# Sheet1.net
KiCad netlist of a schematic drawn in Altium Designer
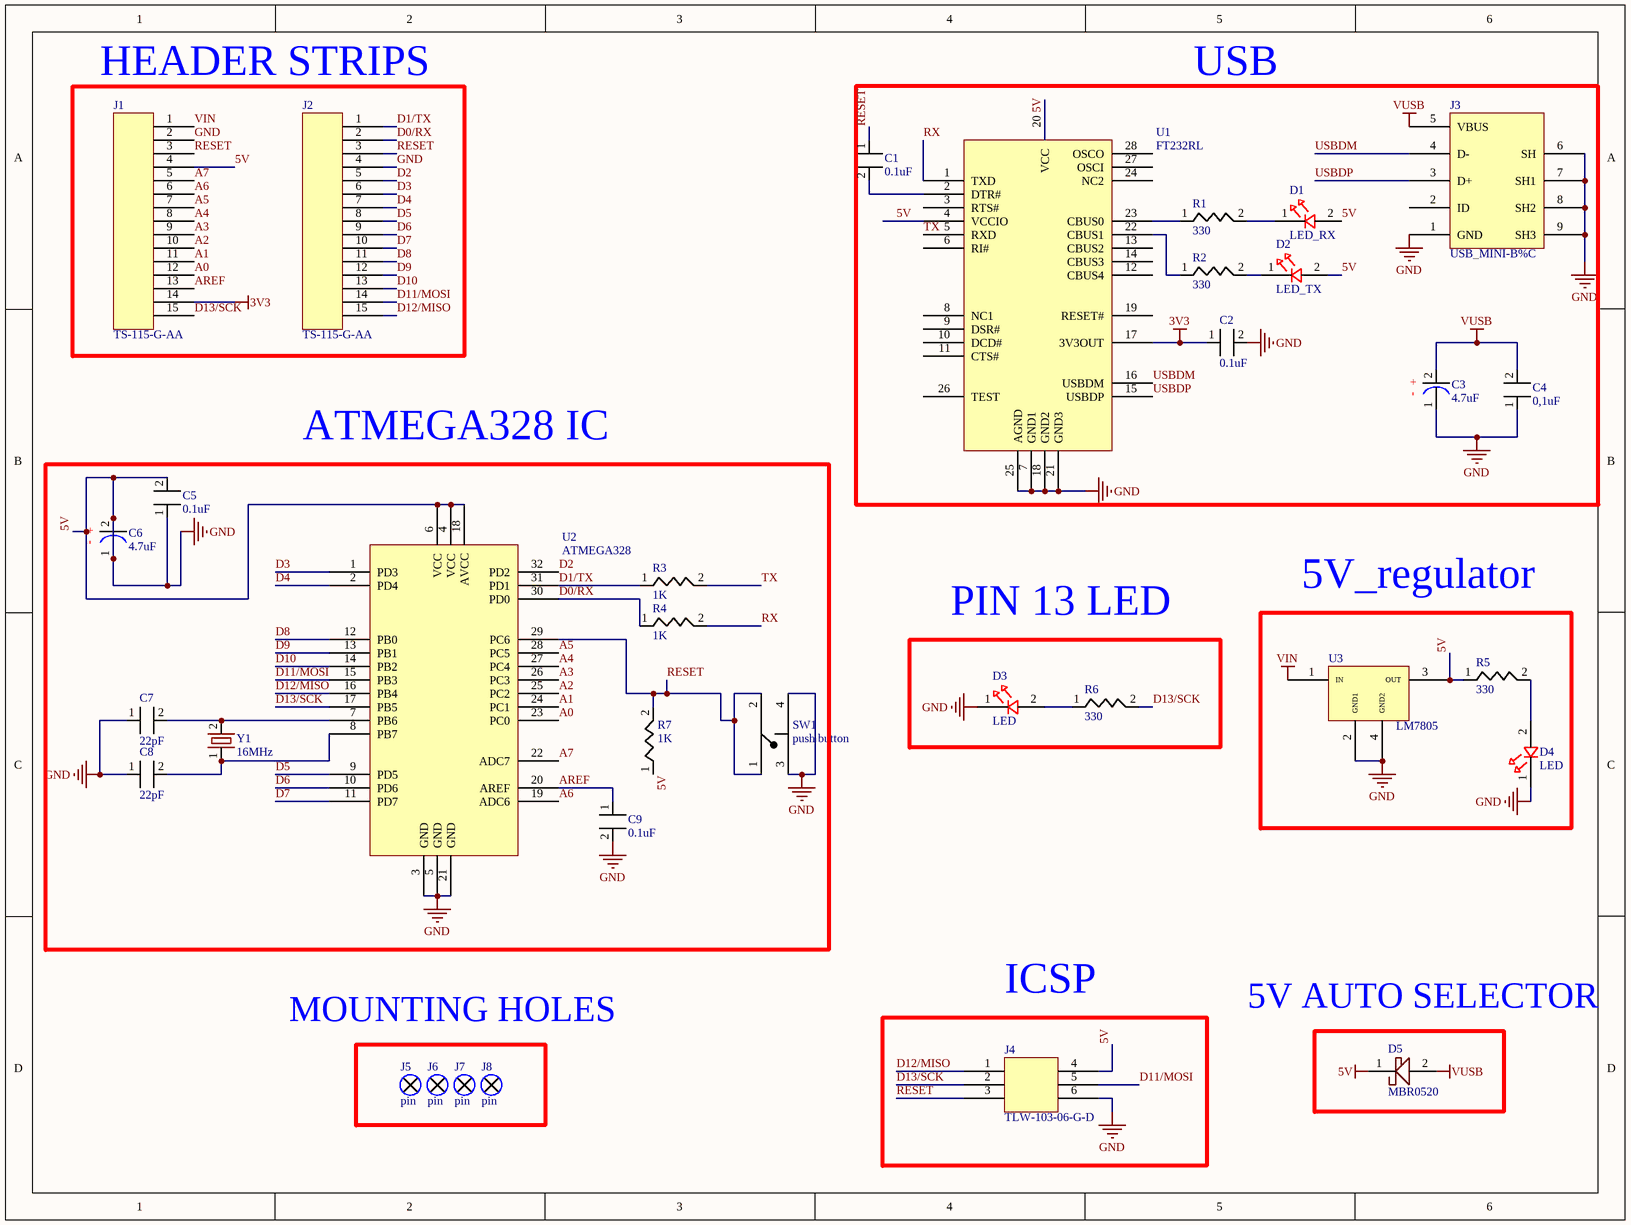
[diagram p0: Sheet1.SchDoc]

(export (version "E")
  (design (tool "Eeschema 10.0.6"))
  (components
    (comp (ref "C1") (value "0.1uF") (footprint "Capacitor") (libsource (lib "Schlib1") (part "capacitor")))
    (comp (ref "C2") (value "0.1uF") (footprint "Capacitor") (libsource (lib "Schlib1") (part "capacitor")))
    (comp (ref "C3")
      (value "4.7uF")
      (footprint "polar Capacitor")
      (libsource (lib "Schlib1") (part "polarized capcitor"))
    )
    (comp (ref "C4") (value "0,1uF") (footprint "Capacitor") (libsource (lib "Schlib1") (part "capacitor")))
    (comp (ref "C5") (value "0.1uF") (footprint "Capacitor") (libsource (lib "Schlib1") (part "capacitor")))
    (comp (ref "C6")
      (value "4.7uF")
      (footprint "polar Capacitor")
      (libsource (lib "Schlib1") (part "polarized capcitor"))
    )
    (comp (ref "C7") (value "22pF") (footprint "Capacitor") (libsource (lib "Schlib1") (part "capacitor")))
    (comp (ref "C8") (value "22pF") (footprint "Capacitor") (libsource (lib "Schlib1") (part "capacitor")))
    (comp (ref "C9") (value "0.1uF") (footprint "Capacitor") (libsource (lib "Schlib1") (part "capacitor")))
    (comp (ref "D1") (value "LED_RX") (footprint "LED") (libsource (lib "Schlib1") (part "LED")))
    (comp (ref "D2") (value "LED_TX") (footprint "LED") (libsource (lib "Schlib1") (part "LED")))
    (comp (ref "D3") (value "LED") (footprint "LED") (libsource (lib "Schlib1") (part "LED")))
    (comp (ref "D4") (value "LED") (footprint "LED") (libsource (lib "Schlib1") (part "LED")))
    (comp (ref "D5") (value "MBR0520") (footprint "MBR0520") (libsource (lib "Schlib1") (part "MBR0520")))
    (comp (ref "J1")
      (value "TS-115-G-AA")
      (footprint "PCBComponent_1")
      (libsource (lib "Schlib1") (part "Component_1"))
    )
    (comp (ref "J2")
      (value "TS-115-G-AA")
      (footprint "PCBComponent_1")
      (libsource (lib "Schlib1") (part "Component_1"))
    )
    (comp (ref "J3")
      (value "USB_MINI-B%C")
      (footprint "USB MINI_B")
      (libsource (lib "Schlib1") (part "USB_MINI-B%C"))
    )
    (comp (ref "J4")
      (value "TLW-103-06-G-D")
      (footprint "pin header3x2")
      (libsource (lib "Schlib1") (part "pin header3x2"))
    )
    (comp (ref "J5") (value "pin") (footprint "PIN") (libsource (lib "Schlib1") (part "pin")))
    (comp (ref "J6") (value "pin") (footprint "PIN") (libsource (lib "Schlib1") (part "pin")))
    (comp (ref "J7") (value "pin") (footprint "PIN") (libsource (lib "Schlib1") (part "pin")))
    (comp (ref "J8") (value "pin") (footprint "PIN") (libsource (lib "Schlib1") (part "pin")))
    (comp (ref "R1") (value "330") (footprint "Resistor") (libsource (lib "Schlib1") (part "resistor")))
    (comp (ref "R2") (value "330") (footprint "Resistor") (libsource (lib "Schlib1") (part "resistor")))
    (comp (ref "R3") (value "1K") (footprint "Resistor") (libsource (lib "Schlib1") (part "resistor")))
    (comp (ref "R4") (value "1K") (footprint "Resistor") (libsource (lib "Schlib1") (part "resistor")))
    (comp (ref "R5") (value "330") (footprint "Resistor") (libsource (lib "Schlib1") (part "resistor")))
    (comp (ref "R6") (value "330") (footprint "Resistor") (libsource (lib "Schlib1") (part "resistor")))
    (comp (ref "R7") (value "1K") (footprint "Resistor") (libsource (lib "Schlib1") (part "resistor")))
    (comp (ref "SW1")
      (value "push button")
      (footprint "push button")
      (libsource (lib "Schlib1") (part "push button"))
    )
    (comp (ref "U1") (value "FT232RL") (footprint "FT232RL") (libsource (lib "Schlib1") (part "FT232RL")))
    (comp (ref "U2")
      (value "ATMEGA328")
      (footprint "ATMEGEA328")
      (libsource (lib "Schlib1") (part "ATMEGA328"))
    )
    (comp (ref "U3") (value "LM7805") (footprint "LM7805") (libsource (lib "Schlib1") (part "regulator")))
    (comp (ref "Y1")
      (value "16MHz")
      (footprint "crystal - duplicate")
      (libsource (lib "Schlib1") (part "crystal_dub"))
    )
  )
  (nets
    (net (code "1") (name "/A0") (class "Default")
      (node (ref "J1") (pin "12") (pinfunction "169_12") (pintype "passive"))
      (node (ref "U2") (pin "23") (pinfunction "PC0_23") (pintype "passive"))
    )
    (net (code "2") (name "/A1") (class "Default")
      (node (ref "J1") (pin "11") (pinfunction "168_11") (pintype "passive"))
      (node (ref "U2") (pin "24") (pinfunction "PC1_24") (pintype "passive"))
    )
    (net (code "3") (name "/A2") (class "Default")
      (node (ref "J1") (pin "10") (pinfunction "167_10") (pintype "passive"))
      (node (ref "U2") (pin "25") (pinfunction "PC2_25") (pintype "passive"))
    )
    (net (code "4") (name "/A3") (class "Default")
      (node (ref "J1") (pin "9") (pinfunction "166_9") (pintype "passive"))
      (node (ref "U2") (pin "26") (pinfunction "PC3_26") (pintype "passive"))
    )
    (net (code "5") (name "/A4") (class "Default")
      (node (ref "J1") (pin "8") (pinfunction "165_8") (pintype "passive"))
      (node (ref "U2") (pin "27") (pinfunction "PC4_27") (pintype "passive"))
    )
    (net (code "6") (name "/A5") (class "Default")
      (node (ref "J1") (pin "7") (pinfunction "164_7") (pintype "passive"))
      (node (ref "U2") (pin "28") (pinfunction "PC5_28") (pintype "passive"))
    )
    (net (code "7") (name "/A6") (class "Default")
      (node (ref "J1") (pin "6") (pinfunction "163_6") (pintype "passive"))
      (node (ref "U2") (pin "19") (pinfunction "ADC6_19") (pintype "passive"))
    )
    (net (code "8") (name "/A7") (class "Default")
      (node (ref "J1") (pin "5") (pinfunction "162_5") (pintype "passive"))
      (node (ref "U2") (pin "22") (pinfunction "ADC7_22") (pintype "passive"))
    )
    (net (code "9") (name "/AREF") (class "Default")
      (node (ref "C9") (pin "1") (pinfunction "155_1") (pintype "passive"))
      (node (ref "J1") (pin "13") (pinfunction "170_13") (pintype "passive"))
      (node (ref "U2") (pin "20") (pinfunction "AREF_20") (pintype "passive"))
    )
    (net (code "10") (name "/D0{slash}RX") (class "Default")
      (node (ref "J2") (pin "2") (pinfunction "159_2") (pintype "passive"))
      (node (ref "R4") (pin "1") (pinfunction "153_1") (pintype "passive"))
      (node (ref "U2") (pin "30") (pinfunction "PD0_30") (pintype "passive"))
    )
    (net (code "11") (name "/D1{slash}TX") (class "Default")
      (node (ref "J2") (pin "1") (pinfunction "158_1") (pintype "passive"))
      (node (ref "R3") (pin "1") (pinfunction "153_1") (pintype "passive"))
      (node (ref "U2") (pin "31") (pinfunction "PD1_31") (pintype "passive"))
    )
    (net (code "12") (name "/D2") (class "Default")
      (node (ref "J2") (pin "5") (pinfunction "162_5") (pintype "passive"))
      (node (ref "U2") (pin "32") (pinfunction "PD2_32") (pintype "passive"))
    )
    (net (code "13") (name "/D3") (class "Default")
      (node (ref "J2") (pin "6") (pinfunction "163_6") (pintype "passive"))
      (node (ref "U2") (pin "1") (pinfunction "PD3_1") (pintype "passive"))
    )
    (net (code "14") (name "/D4") (class "Default")
      (node (ref "J2") (pin "7") (pinfunction "164_7") (pintype "passive"))
      (node (ref "U2") (pin "2") (pinfunction "PD4_2") (pintype "passive"))
    )
    (net (code "15") (name "/D5") (class "Default")
      (node (ref "J2") (pin "8") (pinfunction "165_8") (pintype "passive"))
      (node (ref "U2") (pin "9") (pinfunction "PD5_9") (pintype "passive"))
    )
    (net (code "16") (name "/D6") (class "Default")
      (node (ref "J2") (pin "9") (pinfunction "166_9") (pintype "passive"))
      (node (ref "U2") (pin "10") (pinfunction "PD6_10") (pintype "passive"))
    )
    (net (code "17") (name "/D7") (class "Default")
      (node (ref "J2") (pin "10") (pinfunction "167_10") (pintype "passive"))
      (node (ref "U2") (pin "11") (pinfunction "PD7_11") (pintype "passive"))
    )
    (net (code "18") (name "/D8") (class "Default")
      (node (ref "J2") (pin "11") (pinfunction "168_11") (pintype "passive"))
      (node (ref "U2") (pin "12") (pinfunction "PB0_12") (pintype "passive"))
    )
    (net (code "19") (name "/D9") (class "Default")
      (node (ref "J2") (pin "12") (pinfunction "169_12") (pintype "passive"))
      (node (ref "U2") (pin "13") (pinfunction "PB1_13") (pintype "passive"))
    )
    (net (code "20") (name "/D10") (class "Default")
      (node (ref "J2") (pin "13") (pinfunction "170_13") (pintype "passive"))
      (node (ref "U2") (pin "14") (pinfunction "PB2_14") (pintype "passive"))
    )
    (net (code "21") (name "/D11{slash}MOSI") (class "Default")
      (node (ref "J2") (pin "14") (pinfunction "171_14") (pintype "passive"))
      (node (ref "J4") (pin "5") (pinfunction "14_5") (pintype "passive"))
      (node (ref "U2") (pin "15") (pinfunction "PB3_15") (pintype "passive"))
    )
    (net (code "22") (name "/D12{slash}MISO") (class "Default")
      (node (ref "J2") (pin "15") (pinfunction "172_15") (pintype "passive"))
      (node (ref "J4") (pin "1") (pinfunction "10_1") (pintype "passive"))
      (node (ref "U2") (pin "16") (pinfunction "PB4_16") (pintype "passive"))
    )
    (net (code "23") (name "/D13{slash}SCK") (class "Default")
      (node (ref "J1") (pin "15") (pinfunction "172_15") (pintype "passive"))
      (node (ref "J4") (pin "2") (pinfunction "11_2") (pintype "passive"))
      (node (ref "R6") (pin "2") (pinfunction "152_2") (pintype "passive"))
      (node (ref "U2") (pin "17") (pinfunction "PB5_17") (pintype "passive"))
    )
    (net (code "24") (name "/RESET") (class "Default")
      (node (ref "C1") (pin "1") (pinfunction "155_1") (pintype "passive"))
      (node (ref "J1") (pin "3") (pinfunction "160_3") (pintype "passive"))
      (node (ref "J2") (pin "3") (pinfunction "160_3") (pintype "passive"))
      (node (ref "J4") (pin "3") (pinfunction "12_3") (pintype "passive"))
      (node (ref "R7") (pin "2") (pinfunction "152_2") (pintype "passive"))
      (node (ref "SW1") (pin "1") (pinfunction "254_1") (pintype "passive"))
      (node (ref "SW1") (pin "2") (pinfunction "255_2") (pintype "passive"))
      (node (ref "U2") (pin "29") (pinfunction "PC6_29") (pintype "passive"))
    )
    (net (code "25") (name "/RX") (class "Default")
      (node (ref "R4") (pin "2") (pinfunction "152_2") (pintype "passive"))
      (node (ref "U1") (pin "1") (pinfunction "TXD_1") (pintype "passive"))
    )
    (net (code "26") (name "/TX") (class "Default")
      (node (ref "R3") (pin "2") (pinfunction "152_2") (pintype "passive"))
      (node (ref "U1") (pin "5") (pinfunction "RXD_5") (pintype "passive"))
    )
    (net (code "27") (name "/USBDM") (class "Default")
      (node (ref "J3") (pin "4") (pinfunction "D-_4") (pintype "passive"))
      (node (ref "U1") (pin "16") (pinfunction "USBDM_16") (pintype "passive"))
    )
    (net (code "28") (name "/USBDP") (class "Default")
      (node (ref "J3") (pin "3") (pinfunction "D+_3") (pintype "passive"))
      (node (ref "U1") (pin "15") (pinfunction "USBDP_15") (pintype "passive"))
    )
    (net (code "29") (name "3V3") (class "Default")
      (node (ref "C2") (pin "1") (pinfunction "155_1") (pintype "passive"))
      (node (ref "J1") (pin "14") (pinfunction "171_14") (pintype "passive"))
      (node (ref "U1") (pin "17") (pinfunction "3V3OUT_17") (pintype "passive"))
    )
    (net (code "30") (name "5V") (class "Default")
      (node (ref "C2") (pin "2") (pinfunction "154_2") (pintype "passive"))
      (node (ref "C3") (pin "1") (pinfunction "155_1") (pintype "passive"))
      (node (ref "C4") (pin "1") (pinfunction "155_1") (pintype "passive"))
      (node (ref "C5") (pin "1") (pinfunction "155_1") (pintype "passive"))
      (node (ref "C5") (pin "2") (pinfunction "154_2") (pintype "passive"))
      (node (ref "C6") (pin "1") (pinfunction "155_1") (pintype "passive"))
      (node (ref "C6") (pin "2") (pinfunction "154_2") (pintype "passive"))
      (node (ref "C7") (pin "1") (pinfunction "155_1") (pintype "passive"))
      (node (ref "C8") (pin "1") (pinfunction "155_1") (pintype "passive"))
      (node (ref "C9") (pin "2") (pinfunction "154_2") (pintype "passive"))
      (node (ref "D1") (pin "2") (pinfunction "157_2") (pintype "passive"))
      (node (ref "D2") (pin "2") (pinfunction "157_2") (pintype "passive"))
      (node (ref "D3") (pin "1") (pinfunction "156_1") (pintype "passive"))
      (node (ref "D4") (pin "1") (pinfunction "156_1") (pintype "passive"))
      (node (ref "D5") (pin "1") (pinfunction "180_1") (pintype "passive"))
      (node (ref "J1") (pin "2") (pinfunction "159_2") (pintype "passive"))
      (node (ref "J1") (pin "4") (pinfunction "161_4") (pintype "passive"))
      (node (ref "J2") (pin "4") (pinfunction "161_4") (pintype "passive"))
      (node (ref "J3") (pin "1") (pinfunction "GND_1") (pintype "passive"))
      (node (ref "J3") (pin "6") (pinfunction "SH_6") (pintype "passive"))
      (node (ref "J3") (pin "7") (pinfunction "SH1_7") (pintype "passive"))
      (node (ref "J3") (pin "8") (pinfunction "SH2_8") (pintype "passive"))
      (node (ref "J3") (pin "9") (pinfunction "SH3_9") (pintype "passive"))
      (node (ref "J4") (pin "4") (pinfunction "13_4") (pintype "passive"))
      (node (ref "J4") (pin "6") (pinfunction "6_6") (pintype "passive"))
      (node (ref "R5") (pin "1") (pinfunction "153_1") (pintype "passive"))
      (node (ref "R7") (pin "1") (pinfunction "153_1") (pintype "passive"))
      (node (ref "SW1") (pin "3") (pinfunction "256_3") (pintype "passive"))
      (node (ref "SW1") (pin "4") (pinfunction "257_4") (pintype "passive"))
      (node (ref "U1") (pin "18") (pinfunction "GND2_18") (pintype "passive"))
      (node (ref "U1") (pin "20") (pinfunction "VCC_20") (pintype "passive"))
      (node (ref "U1") (pin "21") (pinfunction "GND3_21") (pintype "passive"))
      (node (ref "U1") (pin "25") (pinfunction "AGND_25") (pintype "passive"))
      (node (ref "U1") (pin "4") (pinfunction "VCCIO_4") (pintype "passive"))
      (node (ref "U1") (pin "7") (pinfunction "GND1_7") (pintype "passive"))
      (node (ref "U2") (pin "18") (pinfunction "AVCC_18") (pintype "passive"))
      (node (ref "U2") (pin "21") (pinfunction "GND_21") (pintype "passive"))
      (node (ref "U2") (pin "3") (pinfunction "GND_3") (pintype "passive"))
      (node (ref "U2") (pin "4") (pinfunction "VCC_4") (pintype "passive"))
      (node (ref "U2") (pin "5") (pinfunction "GND_5") (pintype "passive"))
      (node (ref "U2") (pin "6") (pinfunction "VCC_6") (pintype "passive"))
      (node (ref "U3") (pin "2") (pinfunction "GND1_2") (pintype "passive"))
      (node (ref "U3") (pin "3") (pinfunction "OUT_3") (pintype "passive"))
      (node (ref "U3") (pin "4") (pinfunction "GND2_4") (pintype "passive"))
    )
    (net (code "31") (name "Net-(C1-154)") (class "Default")
      (node (ref "C1") (pin "2") (pinfunction "154_2") (pintype "passive"))
      (node (ref "U1") (pin "2") (pinfunction "DTR#_2") (pintype "passive"))
    )
    (net (code "32") (name "Net-(C7-154)") (class "Default")
      (node (ref "C7") (pin "2") (pinfunction "154_2") (pintype "passive"))
      (node (ref "U2") (pin "7") (pinfunction "PB6_7") (pintype "passive"))
      (node (ref "Y1") (pin "2") (pinfunction "253_2") (pintype "passive"))
    )
    (net (code "33") (name "Net-(C8-154)") (class "Default")
      (node (ref "C8") (pin "2") (pinfunction "154_2") (pintype "passive"))
      (node (ref "U2") (pin "8") (pinfunction "PB7_8") (pintype "passive"))
      (node (ref "Y1") (pin "1") (pinfunction "252_1") (pintype "passive"))
    )
    (net (code "34") (name "Net-(D1-156)") (class "Default")
      (node (ref "D1") (pin "1") (pinfunction "156_1") (pintype "passive"))
      (node (ref "R1") (pin "2") (pinfunction "152_2") (pintype "passive"))
    )
    (net (code "35") (name "Net-(D2-156)") (class "Default")
      (node (ref "D2") (pin "1") (pinfunction "156_1") (pintype "passive"))
      (node (ref "R2") (pin "2") (pinfunction "152_2") (pintype "passive"))
    )
    (net (code "36") (name "Net-(D3-157)") (class "Default")
      (node (ref "D3") (pin "2") (pinfunction "157_2") (pintype "passive"))
      (node (ref "R6") (pin "1") (pinfunction "153_1") (pintype "passive"))
    )
    (net (code "37") (name "Net-(D4-157)") (class "Default")
      (node (ref "D4") (pin "2") (pinfunction "157_2") (pintype "passive"))
      (node (ref "R5") (pin "2") (pinfunction "152_2") (pintype "passive"))
    )
    (net (code "38") (name "Net-(R1-153)") (class "Default")
      (node (ref "R1") (pin "1") (pinfunction "153_1") (pintype "passive"))
      (node (ref "U1") (pin "23") (pinfunction "CBUS0_23") (pintype "passive"))
    )
    (net (code "39") (name "Net-(R2-153)") (class "Default")
      (node (ref "R2") (pin "1") (pinfunction "153_1") (pintype "passive"))
      (node (ref "U1") (pin "22") (pinfunction "CBUS1_22") (pintype "passive"))
    )
    (net (code "40") (name "VIN") (class "Default")
      (node (ref "J1") (pin "1") (pinfunction "158_1") (pintype "passive"))
      (node (ref "U3") (pin "1") (pinfunction "IN_1") (pintype "passive"))
    )
    (net (code "41") (name "VUSB") (class "Default")
      (node (ref "C3") (pin "2") (pinfunction "154_2") (pintype "passive"))
      (node (ref "C4") (pin "2") (pinfunction "154_2") (pintype "passive"))
      (node (ref "D5") (pin "2") (pinfunction "179_2") (pintype "passive"))
      (node (ref "J3") (pin "5") (pinfunction "VBUS_5") (pintype "passive"))
    )
    (net (code "42") (name "unconnected-(J3-ID-Pad2)") (class "Default")
      (node (ref "J3") (pin "2") (pinfunction "ID_2") (pintype "passive"))
    )
    (net (code "43") (name "unconnected-(U1-CBUS2-Pad13)") (class "Default")
      (node (ref "U1") (pin "13") (pinfunction "CBUS2_13") (pintype "passive"))
    )
    (net (code "44") (name "unconnected-(U1-CBUS3-Pad14)") (class "Default")
      (node (ref "U1") (pin "14") (pinfunction "CBUS3_14") (pintype "passive"))
    )
    (net (code "45") (name "unconnected-(U1-CBUS4-Pad12)") (class "Default")
      (node (ref "U1") (pin "12") (pinfunction "CBUS4_12") (pintype "passive"))
    )
    (net (code "46") (name "unconnected-(U1-CTS#-Pad11)") (class "Default")
      (node (ref "U1") (pin "11") (pinfunction "CTS#_11") (pintype "passive"))
    )
    (net (code "47") (name "unconnected-(U1-DCD#-Pad10)") (class "Default")
      (node (ref "U1") (pin "10") (pinfunction "DCD#_10") (pintype "passive"))
    )
    (net (code "48") (name "unconnected-(U1-DSR#-Pad9)") (class "Default")
      (node (ref "U1") (pin "9") (pinfunction "DSR#_9") (pintype "passive"))
    )
    (net (code "49") (name "unconnected-(U1-NC1-Pad8)") (class "Default")
      (node (ref "U1") (pin "8") (pinfunction "NC1_8") (pintype "passive"))
    )
    (net (code "50") (name "unconnected-(U1-NC2-Pad24)") (class "Default")
      (node (ref "U1") (pin "24") (pinfunction "NC2_24") (pintype "passive"))
    )
    (net (code "51") (name "unconnected-(U1-OSCI-Pad27)") (class "Default")
      (node (ref "U1") (pin "27") (pinfunction "OSCI_27") (pintype "passive"))
    )
    (net (code "52") (name "unconnected-(U1-OSCO-Pad28)") (class "Default")
      (node (ref "U1") (pin "28") (pinfunction "OSCO_28") (pintype "passive"))
    )
    (net (code "53") (name "unconnected-(U1-RESET#-Pad19)") (class "Default")
      (node (ref "U1") (pin "19") (pinfunction "RESET#_19") (pintype "passive"))
    )
    (net (code "54") (name "unconnected-(U1-RI#-Pad6)") (class "Default")
      (node (ref "U1") (pin "6") (pinfunction "RI#_6") (pintype "passive"))
    )
    (net (code "55") (name "unconnected-(U1-RTS#-Pad3)") (class "Default")
      (node (ref "U1") (pin "3") (pinfunction "RTS#_3") (pintype "passive"))
    )
    (net (code "56") (name "unconnected-(U1-TEST-Pad26)") (class "Default")
      (node (ref "U1") (pin "26") (pinfunction "TEST_26") (pintype "passive"))
    )
  )
)
